# IdealDiodeSwitcher_2023_05_02_A.net
KiCad netlist of a schematic drawn in EAGLE
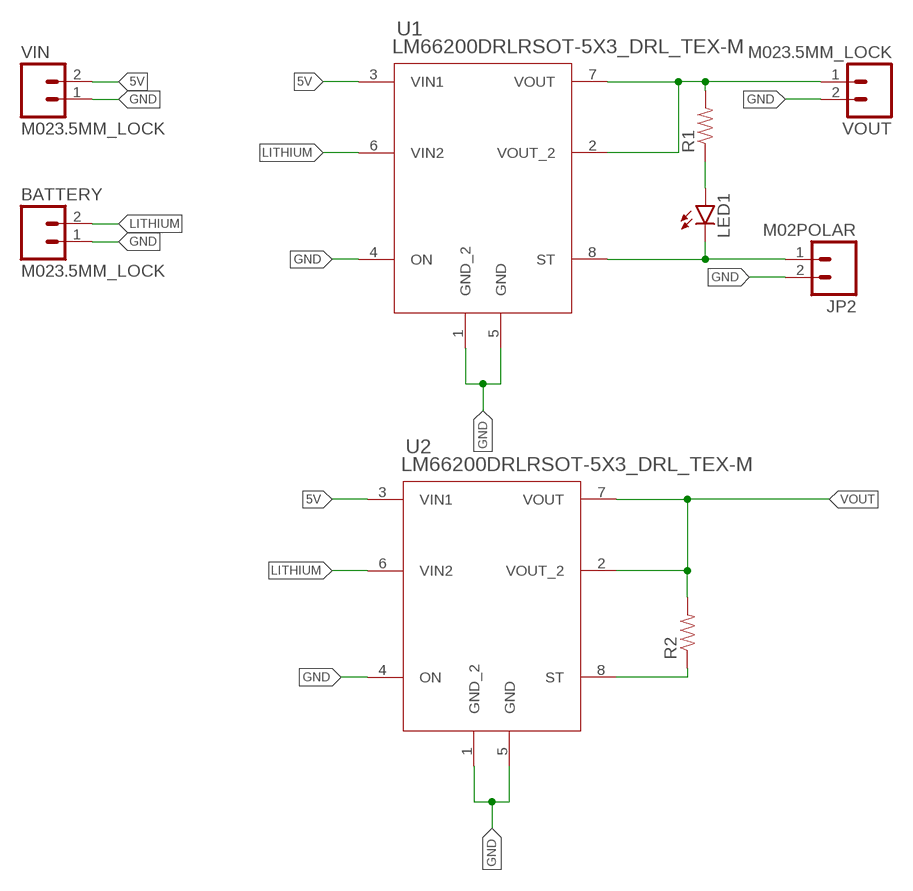
[diagram p0: schematic, sheet 1]

(export (version "E")
  (design (tool "Eeschema 10.0.6"))
  (components
    (comp (ref "BATTERY")
      (value "M023.5MM_LOCK")
      (footprint "eagle-import:SCREWTERMINAL-3.5MM-2_LOCK")
      (libsource (lib "eagle-import") (part "M023.5MM_LOCK"))
    )
    (comp (ref "JP2")
      (value "M02POLAR")
      (footprint "eagle-import:MOLEX-1X2")
      (libsource (lib "eagle-import") (part "M02POLAR"))
    )
    (comp (ref "LED1")
      (value "LED1206")
      (footprint "eagle-import:LED-1206")
      (libsource (lib "eagle-import") (part "LED1206"))
    )
    (comp (ref "R1")
      (value "RESISTOR1206")
      (footprint "eagle-import:1206")
      (libsource (lib "eagle-import") (part "RESISTOR1206"))
    )
    (comp (ref "R2")
      (value "RESISTOR1206")
      (footprint "eagle-import:1206")
      (libsource (lib "eagle-import") (part "RESISTOR1206"))
    )
    (comp (ref "U1")
      (value "LM66200DRLRSOT-5X3_DRL_TEX-M")
      (footprint "eagle-import:SOT-5X3_DRL_TEX-M")
      (fields
        (field (name "MANUFACTURER_PART_NUMBER") "LM66200DRLR")
        (field (name "COPYRIGHT") "Copyright (C) 2023 Ultra Librarian. All rights reserved.")
      )
      (libsource (lib "eagle-import") (part "LM66200DRLRSOT-5X3_DRL_TEX-M"))
    )
    (comp (ref "U2")
      (value "LM66200DRLRSOT-5X3_DRL_TEX-M")
      (footprint "eagle-import:SOT-5X3_DRL_TEX-M")
      (fields
        (field (name "MANUFACTURER_PART_NUMBER") "LM66200DRLR")
        (field (name "COPYRIGHT") "Copyright (C) 2023 Ultra Librarian. All rights reserved.")
      )
      (libsource (lib "eagle-import") (part "LM66200DRLRSOT-5X3_DRL_TEX-M"))
    )
    (comp (ref "VIN")
      (value "M023.5MM_LOCK")
      (footprint "eagle-import:SCREWTERMINAL-3.5MM-2_LOCK")
      (libsource (lib "eagle-import") (part "M023.5MM_LOCK"))
    )
    (comp (ref "VOUT")
      (value "M023.5MM_LOCK")
      (footprint "eagle-import:SCREWTERMINAL-3.5MM-2_LOCK")
      (libsource (lib "eagle-import") (part "M023.5MM_LOCK"))
    )
  )
  (nets
    (net (code "1") (name "5V") (class "Default")
      (node (ref "U1") (pin "3") (pinfunction "VIN1_3") (pintype "input"))
      (node (ref "U2") (pin "3") (pinfunction "VIN1_3") (pintype "input"))
      (node (ref "VIN") (pin "2") (pinfunction "2_2") (pintype "passive"))
    )
    (net (code "2") (name "GND") (class "Default")
      (node (ref "BATTERY") (pin "1") (pinfunction "1_1") (pintype "passive"))
      (node (ref "JP2") (pin "2") (pinfunction "2_2") (pintype "passive"))
      (node (ref "U1") (pin "1") (pinfunction "GND_2_1") (pintype "passive"))
      (node (ref "U1") (pin "4") (pinfunction "ON_4") (pintype "input"))
      (node (ref "U1") (pin "5") (pinfunction "GND_5") (pintype "passive"))
      (node (ref "U2") (pin "1") (pinfunction "GND_2_1") (pintype "passive"))
      (node (ref "U2") (pin "4") (pinfunction "ON_4") (pintype "input"))
      (node (ref "U2") (pin "5") (pinfunction "GND_5") (pintype "passive"))
      (node (ref "VIN") (pin "1") (pinfunction "1_1") (pintype "passive"))
      (node (ref "VOUT") (pin "2") (pinfunction "2_2") (pintype "passive"))
    )
    (net (code "3") (name "LITHIUM") (class "Default")
      (node (ref "BATTERY") (pin "2") (pinfunction "2_2") (pintype "passive"))
      (node (ref "U1") (pin "6") (pinfunction "VIN2_6") (pintype "input"))
      (node (ref "U2") (pin "6") (pinfunction "VIN2_6") (pintype "input"))
    )
    (net (code "4") (name "Net-(LED1-PadA)") (class "Default")
      (node (ref "LED1") (pin "A") (pinfunction "A_A") (pintype "passive"))
      (node (ref "R1") (pin "1") (pinfunction "1_1") (pintype "passive"))
    )
    (net (code "5") (name "Net-(U1-ST)") (class "Default")
      (node (ref "JP2") (pin "1") (pinfunction "1_1") (pintype "passive"))
      (node (ref "LED1") (pin "C") (pinfunction "C_C") (pintype "passive"))
      (node (ref "U1") (pin "8") (pinfunction "ST_8") (pintype "output"))
    )
    (net (code "6") (name "Net-(U2-ST)") (class "Default")
      (node (ref "R2") (pin "1") (pinfunction "1_1") (pintype "passive"))
      (node (ref "U2") (pin "8") (pinfunction "ST_8") (pintype "output"))
    )
    (net (code "7") (name "VOUT") (class "Default")
      (node (ref "R1") (pin "2") (pinfunction "2_2") (pintype "passive"))
      (node (ref "R2") (pin "2") (pinfunction "2_2") (pintype "passive"))
      (node (ref "U1") (pin "2") (pinfunction "VOUT_2_2") (pintype "power_in"))
      (node (ref "U1") (pin "7") (pinfunction "VOUT_7") (pintype "output"))
      (node (ref "U2") (pin "2") (pinfunction "VOUT_2_2") (pintype "power_in"))
      (node (ref "U2") (pin "7") (pinfunction "VOUT_7") (pintype "output"))
      (node (ref "VOUT") (pin "1") (pinfunction "1_1") (pintype "passive"))
    )
  )
)
